# I2C_Conventor.net
KiCad netlist of a schematic drawn in Altium Designer
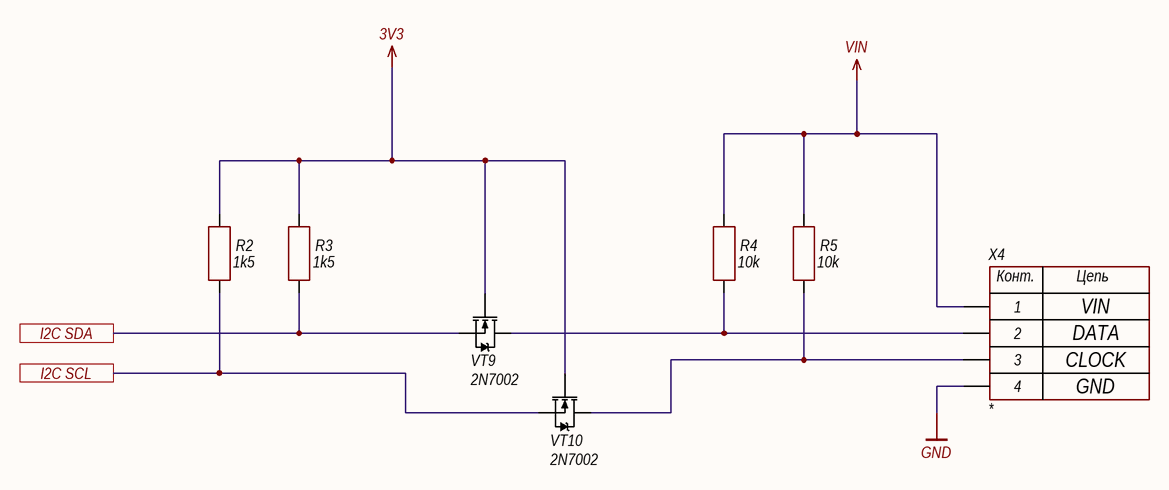
[diagram p0: I2C Conventor.SchDoc]

(export (version "E")
  (design (tool "Eeschema 10.0.6"))
  (components
    (comp (ref "R2") (value "1k5") (footprint "CH0603R") (libsource (lib "Discrete") (part "Resistor")))
    (comp (ref "R3") (value "1k5") (footprint "CH0603R") (libsource (lib "Discrete") (part "Resistor")))
    (comp (ref "R4") (value "10k") (footprint "CH0603R") (libsource (lib "Discrete") (part "Resistor")))
    (comp (ref "R5") (value "10k") (footprint "CH0603R") (libsource (lib "Discrete") (part "Resistor")))
    (comp (ref "VT9")
      (value "2N7002")
      (footprint "SOT23_123")
      (description "Mosfet")
      (fields (field (name "MANUFACTURER") "ON Semiconductor"))
      (libsource (lib "Transistor") (part "N-chanel"))
    )
    (comp (ref "VT10")
      (value "2N7002")
      (footprint "SOT23_123")
      (description "Mosfet")
      (fields (field (name "MANUFACTURER") "ON Semiconductor"))
      (libsource (lib "Transistor") (part "N-chanel"))
    )
    (comp (ref "X4") (value "*") (footprint "CON: PLS-4") (libsource (lib "Connectors") (part "4-Connector")))
  )
  (nets
    (net (code "1") (name "/I2C SCL") (class "Default")
      (node (ref "R2") (pin "1") (pinfunction "1_1") (pintype "passive"))
      (node (ref "VT10") (pin "3") (pinfunction "S_3") (pintype "passive"))
    )
    (net (code "2") (name "/I2C SDA") (class "Default")
      (node (ref "R3") (pin "1") (pinfunction "1_1") (pintype "passive"))
      (node (ref "VT9") (pin "3") (pinfunction "S_3") (pintype "passive"))
    )
    (net (code "3") (name "3V3") (class "Default")
      (node (ref "R2") (pin "2") (pinfunction "2_2") (pintype "passive"))
      (node (ref "R3") (pin "2") (pinfunction "2_2") (pintype "passive"))
      (node (ref "VT10") (pin "1") (pinfunction "G_1") (pintype "passive"))
      (node (ref "VT9") (pin "1") (pinfunction "G_1") (pintype "passive"))
    )
    (net (code "4") (name "GND") (class "Default")
      (node (ref "X4") (pin "4") (pinfunction "4_4") (pintype "power_in"))
    )
    (net (code "5") (name "Net-(VT9-D)") (class "Default")
      (node (ref "R4") (pin "1") (pinfunction "1_1") (pintype "passive"))
      (node (ref "VT9") (pin "2") (pinfunction "D_2") (pintype "passive"))
      (node (ref "X4") (pin "2") (pinfunction "2_2") (pintype "passive"))
    )
    (net (code "6") (name "Net-(VT10-D)") (class "Default")
      (node (ref "R5") (pin "1") (pinfunction "1_1") (pintype "passive"))
      (node (ref "VT10") (pin "2") (pinfunction "D_2") (pintype "passive"))
      (node (ref "X4") (pin "3") (pinfunction "3_3") (pintype "power_in"))
    )
    (net (code "7") (name "VIN") (class "Default")
      (node (ref "R4") (pin "2") (pinfunction "2_2") (pintype "passive"))
      (node (ref "R5") (pin "2") (pinfunction "2_2") (pintype "passive"))
      (node (ref "X4") (pin "1") (pinfunction "1_1") (pintype "passive"))
    )
  )
)
